# Battery_Manager.net
KiCad netlist of a schematic drawn in Altium Designer
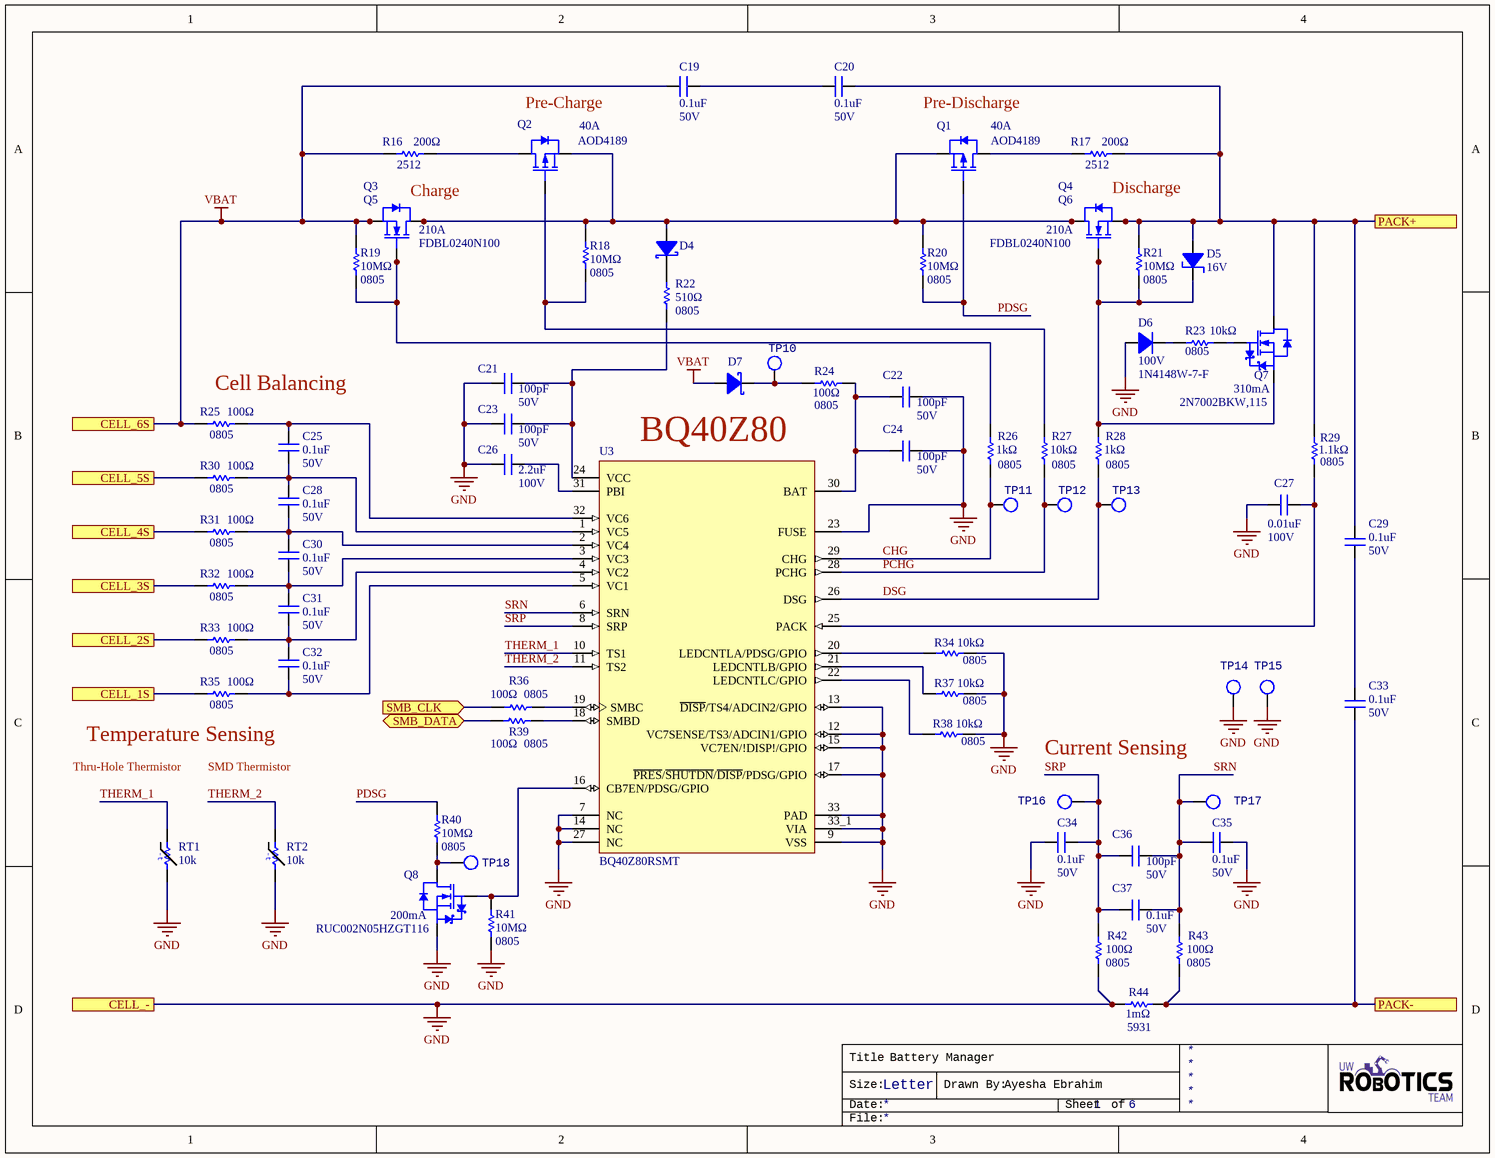
[diagram p0: Battery Manager.SchDoc]

(export (version "E")
  (design (tool "Eeschema 10.0.6"))
  (components
    (comp (ref "C19")
      (value "0.1uF")
      (footprint "CAPC2012X140N")
      (description "CAP CER 0.1UF 50V X7R 0805")
      (fields
        (field (name "TOLERANCE") "10%")
        (field (name "VOLTAGE RATING") "50V")
        (field (name "Comment") "CAP_0.1uF_50V_0805")
      )
      (libsource (lib "UWRT_Schematic_Library_2020") (part "CAP_0.1uF_50V_0805"))
    )
    (comp (ref "C20")
      (value "0.1uF")
      (footprint "CAPC2012X140N")
      (description "CAP CER 0.1UF 50V X7R 0805")
      (fields
        (field (name "TOLERANCE") "10%")
        (field (name "VOLTAGE RATING") "50V")
        (field (name "Comment") "CAP_0.1uF_50V_0805")
      )
      (libsource (lib "UWRT_Schematic_Library_2020") (part "CAP_0.1uF_50V_0805"))
    )
    (comp (ref "C21")
      (value "100pF")
      (footprint "CAPC2012X140N")
      (description "CAP CER 100PF 50V C0G/NP0 0805")
      (fields
        (field (name "TOLERANCE") "5%")
        (field (name "VOLTAGE RATING") "50V")
        (field (name "Comment") "CAP_100pF_50V_0805")
      )
      (libsource (lib "UWRT_Schematic_Library_2020") (part "CAP_100pF_50V_0805"))
    )
    (comp (ref "C22")
      (value "100pF")
      (footprint "CAPC2012X140N")
      (description "CAP CER 100PF 50V C0G/NP0 0805")
      (fields
        (field (name "TOLERANCE") "5%")
        (field (name "VOLTAGE RATING") "50V")
        (field (name "Comment") "CAP_100pF_50V_0805")
      )
      (libsource (lib "UWRT_Schematic_Library_2020") (part "CAP_100pF_50V_0805"))
    )
    (comp (ref "C23")
      (value "100pF")
      (footprint "CAPC2012X140N")
      (description "CAP CER 100PF 50V C0G/NP0 0805")
      (fields
        (field (name "TOLERANCE") "5%")
        (field (name "VOLTAGE RATING") "50V")
        (field (name "Comment") "CAP_100pF_50V_0805")
      )
      (libsource (lib "UWRT_Schematic_Library_2020") (part "CAP_100pF_50V_0805"))
    )
    (comp (ref "C24")
      (value "100pF")
      (footprint "CAPC2012X140N")
      (description "CAP CER 100PF 50V C0G/NP0 0805")
      (fields
        (field (name "TOLERANCE") "5%")
        (field (name "VOLTAGE RATING") "50V")
        (field (name "Comment") "CAP_100pF_50V_0805")
      )
      (libsource (lib "UWRT_Schematic_Library_2020") (part "CAP_100pF_50V_0805"))
    )
    (comp (ref "C25")
      (value "0.1uF")
      (footprint "CAPC2012X140N")
      (description "CAP CER 0.1UF 50V X7R 0805")
      (fields
        (field (name "TOLERANCE") "10%")
        (field (name "VOLTAGE RATING") "50V")
        (field (name "Comment") "CAP_0.1uF_50V_0805")
      )
      (libsource (lib "UWRT_Schematic_Library_2020") (part "CAP_0.1uF_50V_0805"))
    )
    (comp (ref "C26")
      (value "2.2uF")
      (footprint "CAPC1210(3225)")
      (description "CAP CER 2.2UF 100V X7R 1210")
      (fields
        (field (name "TOLERANCE") "10%")
        (field (name "VOLTAGE RATING") "100V")
        (field (name "Comment") "CAP_2.2uF_100V_1210")
      )
      (libsource (lib "UWRT_Schematic_Library_2020") (part "CAP_2.2uF_100V_1210"))
    )
    (comp (ref "C27")
      (value "0.01uF")
      (footprint "CAPC2012X140N")
      (description "CAP CER 10000PF 100V X7R 0805")
      (fields
        (field (name "TOLERANCE") "10%")
        (field (name "VOLTAGE RATING") "100V")
        (field (name "Comment") "CAP_0.01uF_100V_0805")
      )
      (libsource (lib "UWRT_Schematic_Library_2020") (part "CAP_0.01uF_100V_0805"))
    )
    (comp (ref "C28")
      (value "0.1uF")
      (footprint "CAPC2012X140N")
      (description "CAP CER 0.1UF 50V X7R 0805")
      (fields
        (field (name "TOLERANCE") "10%")
        (field (name "VOLTAGE RATING") "50V")
        (field (name "Comment") "CAP_0.1uF_50V_0805")
      )
      (libsource (lib "UWRT_Schematic_Library_2020") (part "CAP_0.1uF_50V_0805"))
    )
    (comp (ref "C29")
      (value "0.1uF")
      (footprint "CAPC2012X140N")
      (description "CAP CER 0.1UF 50V X7R 0805")
      (fields
        (field (name "TOLERANCE") "10%")
        (field (name "VOLTAGE RATING") "50V")
        (field (name "Comment") "CAP_0.1uF_50V_0805")
      )
      (libsource (lib "UWRT_Schematic_Library_2020") (part "CAP_0.1uF_50V_0805"))
    )
    (comp (ref "C30")
      (value "0.1uF")
      (footprint "CAPC2012X140N")
      (description "CAP CER 0.1UF 50V X7R 0805")
      (fields
        (field (name "TOLERANCE") "10%")
        (field (name "VOLTAGE RATING") "50V")
        (field (name "Comment") "CAP_0.1uF_50V_0805")
      )
      (libsource (lib "UWRT_Schematic_Library_2020") (part "CAP_0.1uF_50V_0805"))
    )
    (comp (ref "C31")
      (value "0.1uF")
      (footprint "CAPC2012X140N")
      (description "CAP CER 0.1UF 50V X7R 0805")
      (fields
        (field (name "TOLERANCE") "10%")
        (field (name "VOLTAGE RATING") "50V")
        (field (name "Comment") "CAP_0.1uF_50V_0805")
      )
      (libsource (lib "UWRT_Schematic_Library_2020") (part "CAP_0.1uF_50V_0805"))
    )
    (comp (ref "C32")
      (value "0.1uF")
      (footprint "CAPC2012X140N")
      (description "CAP CER 0.1UF 50V X7R 0805")
      (fields
        (field (name "TOLERANCE") "10%")
        (field (name "VOLTAGE RATING") "50V")
        (field (name "Comment") "CAP_0.1uF_50V_0805")
      )
      (libsource (lib "UWRT_Schematic_Library_2020") (part "CAP_0.1uF_50V_0805"))
    )
    (comp (ref "C33")
      (value "0.1uF")
      (footprint "CAPC2012X140N")
      (description "CAP CER 0.1UF 50V X7R 0805")
      (fields
        (field (name "TOLERANCE") "10%")
        (field (name "VOLTAGE RATING") "50V")
        (field (name "Comment") "CAP_0.1uF_50V_0805")
      )
      (libsource (lib "UWRT_Schematic_Library_2020") (part "CAP_0.1uF_50V_0805"))
    )
    (comp (ref "C34")
      (value "0.1uF")
      (footprint "CAPC2012X140N")
      (description "CAP CER 0.1UF 50V X7R 0805")
      (fields
        (field (name "TOLERANCE") "10%")
        (field (name "VOLTAGE RATING") "50V")
        (field (name "Comment") "CAP_0.1uF_50V_0805")
      )
      (libsource (lib "UWRT_Schematic_Library_2020") (part "CAP_0.1uF_50V_0805"))
    )
    (comp (ref "C35")
      (value "0.1uF")
      (footprint "CAPC2012X140N")
      (description "CAP CER 0.1UF 50V X7R 0805")
      (fields
        (field (name "TOLERANCE") "10%")
        (field (name "VOLTAGE RATING") "50V")
        (field (name "Comment") "CAP_0.1uF_50V_0805")
      )
      (libsource (lib "UWRT_Schematic_Library_2020") (part "CAP_0.1uF_50V_0805"))
    )
    (comp (ref "C36")
      (value "100pF")
      (footprint "CAPC2012X140N")
      (description "CAP CER 100PF 50V C0G/NP0 0805")
      (fields
        (field (name "TOLERANCE") "5%")
        (field (name "VOLTAGE RATING") "50V")
        (field (name "Comment") "CAP_100pF_50V_0805")
      )
      (libsource (lib "UWRT_Schematic_Library_2020") (part "CAP_100pF_50V_0805"))
    )
    (comp (ref "C37")
      (value "0.1uF")
      (footprint "CAPC2012X140N")
      (description "CAP CER 0.1UF 50V X7R 0805")
      (fields
        (field (name "TOLERANCE") "10%")
        (field (name "VOLTAGE RATING") "50V")
        (field (name "Comment") "CAP_0.1uF_50V_0805")
      )
      (libsource (lib "UWRT_Schematic_Library_2020") (part "CAP_0.1uF_50V_0805"))
    )
    (comp (ref "D4")
      (value "B0540W-7-F")
      (footprint "SOD-123_FLAT")
      (description "DIODE SCHOTTKY 40V 500MA SOD123")
      (fields
        (field (name "MANUFACTURER") "Diodes Inc.")
        (field (name "OCTOPART") "https://octopart.com/b0540w-7-f-diodes+inc.-325656")
      )
      (libsource (lib "UWRT_Schematic_Library_2020") (part "DIO_SCHOTTKY_40V_500mA"))
    )
    (comp (ref "D5")
      (value "DIO_ZENER_16V")
      (footprint "SOD-123_FLAT")
      (description "DIODE ZENER 16V 500MW SOD123")
      (fields (field (name "ZENER VOLTAGE") "16V") (field (name "TOLERANCE") "5%"))
      (libsource (lib "UWRT_Schematic_Library_2020") (part "DIO_ZENER_16V"))
    )
    (comp (ref "D6")
      (value "100V")
      (footprint "SOD-123_FLAT")
      (description "DIODE GEN PURP 100V 300MA SOD123")
      (fields
        (field (name "MANUFACTURER PART NUMBER 1") "1N4148W-7-F")
        (field (name "Comment") "1N4148W-7-F")
      )
      (libsource (lib "UWRT_Schematic_Library_2020") (part "DIO_100V_300mA"))
    )
    (comp (ref "D7")
      (value "B0540W-7-F")
      (footprint "SOD-123_FLAT")
      (description "DIODE SCHOTTKY 40V 500MA SOD123")
      (fields
        (field (name "MANUFACTURER") "Diodes Inc.")
        (field (name "OCTOPART") "https://octopart.com/b0540w-7-f-diodes+inc.-325656")
      )
      (libsource (lib "UWRT_Schematic_Library_2020") (part "DIO_SCHOTTKY_40V_500mA"))
    )
    (comp (ref "Q1")
      (value "PMOS_40V_40A")
      (footprint "D-PAK")
      (description "MOSFET P-CH 40V 40A TO252")
      (fields (field (name "MANUFACTURER PART NUMBER 1") "AOD4189") (field (name "ID") "40A"))
      (libsource (lib "UWRT_Schematic_Library_2020") (part "PMOS_40V_40A"))
    )
    (comp (ref "Q2")
      (value "PMOS_40V_40A")
      (footprint "D-PAK")
      (description "MOSFET P-CH 40V 40A TO252")
      (fields (field (name "MANUFACTURER PART NUMBER 1") "AOD4189") (field (name "ID") "40A"))
      (libsource (lib "UWRT_Schematic_Library_2020") (part "PMOS_40V_40A"))
    )
    (comp (ref "Q3")
      (value "NMOS_100V_210A")
      (footprint "8-HPSOF")
      (description "MOSFET N-CH 100V 210A POWER56")
      (fields (field (name "MANUFACTURER PART NUMBER 1") "FDBL0240N100") (field (name "ID") "210A"))
      (libsource (lib "UWRT_Schematic_Library_2020") (part "NMOS_100V_210A"))
    )
    (comp (ref "Q4")
      (value "NMOS_100V_210A")
      (footprint "8-HPSOF")
      (description "MOSFET N-CH 100V 210A POWER56")
      (fields (field (name "MANUFACTURER PART NUMBER 1") "FDBL0240N100") (field (name "ID") "210A"))
      (libsource (lib "UWRT_Schematic_Library_2020") (part "NMOS_100V_210A"))
    )
    (comp (ref "Q5")
      (value "NMOS_100V_210A")
      (footprint "8-HPSOF")
      (description "MOSFET N-CH 100V 210A POWER56")
      (libsource (lib "UWRT_Schematic_Library_2020") (part "NMOS_100V_210A"))
    )
    (comp (ref "Q6")
      (value "NMOS_100V_210A")
      (footprint "8-HPSOF")
      (description "MOSFET N-CH 100V 210A POWER56")
      (libsource (lib "UWRT_Schematic_Library_2020") (part "NMOS_100V_210A"))
    )
    (comp (ref "Q7")
      (value "NMOS_60V_310mA")
      (footprint "SOT323")
      (description "NMOS N-CH 60V 310mA SOT-323")
      (fields (field (name "MANUFACTURER PART NUMBER 1") "2N7002BKW,115") (field (name "ID") "310mA"))
      (libsource (lib "UWRT_Schematic_Library_2020") (part "NMOS_60V_310mA"))
    )
    (comp (ref "Q8")
      (value "NMOS_50V_200mA")
      (footprint "SOT23-3")
      (description "NMOS N-CH 50V 200mA 1.2V DRIVE SOT-23-3")
      (fields (field (name "MANUFACTURER PART NUMBER 1") "RUC002N05HZGT116") (field (name "ID") "200mA"))
      (libsource (lib "UWRT_Schematic_Library_2020") (part "NMOS_50V_200mA"))
    )
    (comp (ref "R16")
      (value "200Ω")
      (footprint "RESC6532X75N")
      (description "RES 200 OHM 5% 1W 2512")
      (fields
        (field (name "PACKAGE") "2512")
        (field (name "TOLERANCE") "5%")
        (field (name "Comment") "RES_200Ω_2512")
      )
      (libsource (lib "UWRT_Schematic_Library_2020") (part "RES_200Ω_2512"))
    )
    (comp (ref "R17")
      (value "200Ω")
      (footprint "RESC6532X75N")
      (description "RES 200 OHM 5% 1W 2512")
      (fields
        (field (name "PACKAGE") "2512")
        (field (name "TOLERANCE") "5%")
        (field (name "Comment") "RES_200Ω_2512")
      )
      (libsource (lib "UWRT_Schematic_Library_2020") (part "RES_200Ω_2512"))
    )
    (comp (ref "R18")
      (value "10MΩ")
      (footprint "RESC2012X60N")
      (description "RES SMD 10M OHM 5% 1/8W 0805")
      (fields
        (field (name "TOLERANCE") "5%")
        (field (name "CASE CODE (IMPERIAL)") "0805")
        (field (name "Comment") "RES_10MΩ_0805")
      )
      (libsource (lib "UWRT_Schematic_Library_2020") (part "RES_10MΩ_0805"))
    )
    (comp (ref "R19")
      (value "10MΩ")
      (footprint "RESC2012X60N")
      (description "RES SMD 10M OHM 5% 1/8W 0805")
      (fields
        (field (name "TOLERANCE") "5%")
        (field (name "CASE CODE (IMPERIAL)") "0805")
        (field (name "Comment") "RES_10MΩ_0805")
      )
      (libsource (lib "UWRT_Schematic_Library_2020") (part "RES_10MΩ_0805"))
    )
    (comp (ref "R20")
      (value "10MΩ")
      (footprint "RESC2012X60N")
      (description "RES SMD 10M OHM 5% 1/8W 0805")
      (fields
        (field (name "TOLERANCE") "5%")
        (field (name "CASE CODE (IMPERIAL)") "0805")
        (field (name "Comment") "RES_10MΩ_0805")
      )
      (libsource (lib "UWRT_Schematic_Library_2020") (part "RES_10MΩ_0805"))
    )
    (comp (ref "R21")
      (value "10MΩ")
      (footprint "RESC2012X60N")
      (description "RES SMD 10M OHM 5% 1/8W 0805")
      (fields
        (field (name "TOLERANCE") "5%")
        (field (name "CASE CODE (IMPERIAL)") "0805")
        (field (name "Comment") "RES_10MΩ_0805")
      )
      (libsource (lib "UWRT_Schematic_Library_2020") (part "RES_10MΩ_0805"))
    )
    (comp (ref "R22")
      (value "510Ω")
      (footprint "RESC2012X60N")
      (description "RES SMD 510 OHM 1% 1/8W 0805")
      (fields
        (field (name "CASE CODE (IMPERIAL)") "0805")
        (field (name "TOLERANCE") "1%")
        (field (name "Comment") "RES_510Ω_0805")
      )
      (libsource (lib "UWRT_Schematic_Library_2020") (part "RES_510Ω_0805"))
    )
    (comp (ref "R23")
      (value "10kΩ")
      (footprint "RESC2012X60N")
      (description "RES SMD 10K OHM 1% 1/8W 0805")
      (fields
        (field (name "CASE CODE (IMPERIAL)") "0805")
        (field (name "TOLERANCE") "1%")
        (field (name "Comment") "RES_10kΩ_0805")
      )
      (libsource (lib "UWRT_Schematic_Library_2020") (part "RES_10kΩ_0805"))
    )
    (comp (ref "R24")
      (value "100Ω")
      (footprint "RESC2012X60N")
      (description "RES SMD 100 OHM 1% 1/8W 0805")
      (fields (field (name "CASE CODE (IMPERIAL)") "0805") (field (name "Comment") "RES_100Ω_0805"))
      (libsource (lib "UWRT_Schematic_Library_2020") (part "RES_100Ω_0805"))
    )
    (comp (ref "R25")
      (value "100Ω")
      (footprint "RESC2012X60N")
      (description "RES SMD 100 OHM 1% 1/8W 0805")
      (fields (field (name "CASE CODE (IMPERIAL)") "0805") (field (name "Comment") "RES_100Ω_0805"))
      (libsource (lib "UWRT_Schematic_Library_2020") (part "RES_100Ω_0805"))
    )
    (comp (ref "R26")
      (value "1kΩ")
      (footprint "RESC2012X60N")
      (description "RES SMD 1K OHM 1% 1/8W 0805")
      (fields
        (field (name "CASE CODE (IMPERIAL)") "0805")
        (field (name "TOLERANCE") "1%")
        (field (name "Comment") "RES_1kΩ_0805")
      )
      (libsource (lib "UWRT_Schematic_Library_2020") (part "RES_1kΩ_0805"))
    )
    (comp (ref "R27")
      (value "10kΩ")
      (footprint "RESC2012X60N")
      (description "RES SMD 10K OHM 1% 1/8W 0805")
      (fields
        (field (name "CASE CODE (IMPERIAL)") "0805")
        (field (name "TOLERANCE") "1%")
        (field (name "Comment") "RES_10kΩ_0805")
      )
      (libsource (lib "UWRT_Schematic_Library_2020") (part "RES_10kΩ_0805"))
    )
    (comp (ref "R28")
      (value "1kΩ")
      (footprint "RESC2012X60N")
      (description "RES SMD 1K OHM 1% 1/8W 0805")
      (fields
        (field (name "CASE CODE (IMPERIAL)") "0805")
        (field (name "TOLERANCE") "1%")
        (field (name "Comment") "RES_1kΩ_0805")
      )
      (libsource (lib "UWRT_Schematic_Library_2020") (part "RES_1kΩ_0805"))
    )
    (comp (ref "R29")
      (value "1.1kΩ")
      (footprint "RESC2012X60N")
      (description "RES SMD 1.1K OHM 1% 1/8W 0805")
      (fields
        (field (name "CASE CODE (IMPERIAL)") "0805")
        (field (name "TOLERANCE") "1%")
        (field (name "Comment") "RES_1.1kΩ_0805")
      )
      (libsource (lib "UWRT_Schematic_Library_2020") (part "RES_1.1kΩ_0805"))
    )
    (comp (ref "R30")
      (value "100Ω")
      (footprint "RESC2012X60N")
      (description "RES SMD 100 OHM 1% 1/8W 0805")
      (fields (field (name "CASE CODE (IMPERIAL)") "0805") (field (name "Comment") "RES_100Ω_0805"))
      (libsource (lib "UWRT_Schematic_Library_2020") (part "RES_100Ω_0805"))
    )
    (comp (ref "R31")
      (value "100Ω")
      (footprint "RESC2012X60N")
      (description "RES SMD 100 OHM 1% 1/8W 0805")
      (fields (field (name "CASE CODE (IMPERIAL)") "0805") (field (name "Comment") "RES_100Ω_0805"))
      (libsource (lib "UWRT_Schematic_Library_2020") (part "RES_100Ω_0805"))
    )
    (comp (ref "R32")
      (value "100Ω")
      (footprint "RESC2012X60N")
      (description "RES SMD 100 OHM 1% 1/8W 0805")
      (fields (field (name "CASE CODE (IMPERIAL)") "0805") (field (name "Comment") "RES_100Ω_0805"))
      (libsource (lib "UWRT_Schematic_Library_2020") (part "RES_100Ω_0805"))
    )
    (comp (ref "R33")
      (value "100Ω")
      (footprint "RESC2012X60N")
      (description "RES SMD 100 OHM 1% 1/8W 0805")
      (fields (field (name "CASE CODE (IMPERIAL)") "0805") (field (name "Comment") "RES_100Ω_0805"))
      (libsource (lib "UWRT_Schematic_Library_2020") (part "RES_100Ω_0805"))
    )
    (comp (ref "R34")
      (value "10kΩ")
      (footprint "RESC2012X60N")
      (description "RES SMD 10K OHM 1% 1/8W 0805")
      (fields
        (field (name "CASE CODE (IMPERIAL)") "0805")
        (field (name "TOLERANCE") "1%")
        (field (name "Comment") "RES_10kΩ_0805")
      )
      (libsource (lib "UWRT_Schematic_Library_2020") (part "RES_10kΩ_0805"))
    )
    (comp (ref "R35")
      (value "100Ω")
      (footprint "RESC2012X60N")
      (description "RES SMD 100 OHM 1% 1/8W 0805")
      (fields (field (name "CASE CODE (IMPERIAL)") "0805") (field (name "Comment") "RES_100Ω_0805"))
      (libsource (lib "UWRT_Schematic_Library_2020") (part "RES_100Ω_0805"))
    )
    (comp (ref "R36")
      (value "100Ω")
      (footprint "RESC2012X60N")
      (description "RES SMD 100 OHM 1% 1/8W 0805")
      (fields (field (name "CASE CODE (IMPERIAL)") "0805") (field (name "Comment") "RES_100Ω_0805"))
      (libsource (lib "UWRT_Schematic_Library_2020") (part "RES_100Ω_0805"))
    )
    (comp (ref "R37")
      (value "10kΩ")
      (footprint "RESC2012X60N")
      (description "RES SMD 10K OHM 1% 1/8W 0805")
      (fields
        (field (name "CASE CODE (IMPERIAL)") "0805")
        (field (name "TOLERANCE") "1%")
        (field (name "Comment") "RES_10kΩ_0805")
      )
      (libsource (lib "UWRT_Schematic_Library_2020") (part "RES_10kΩ_0805"))
    )
    (comp (ref "R38")
      (value "10kΩ")
      (footprint "RESC2012X60N")
      (description "RES SMD 10K OHM 1% 1/8W 0805")
      (fields
        (field (name "CASE CODE (IMPERIAL)") "0805")
        (field (name "TOLERANCE") "1%")
        (field (name "Comment") "RES_10kΩ_0805")
      )
      (libsource (lib "UWRT_Schematic_Library_2020") (part "RES_10kΩ_0805"))
    )
    (comp (ref "R39")
      (value "100Ω")
      (footprint "RESC2012X60N")
      (description "RES SMD 100 OHM 1% 1/8W 0805")
      (fields (field (name "CASE CODE (IMPERIAL)") "0805") (field (name "Comment") "RES_100Ω_0805"))
      (libsource (lib "UWRT_Schematic_Library_2020") (part "RES_100Ω_0805"))
    )
    (comp (ref "R40")
      (value "10MΩ")
      (footprint "RESC2012X60N")
      (description "RES SMD 10M OHM 5% 1/8W 0805")
      (fields
        (field (name "TOLERANCE") "5%")
        (field (name "CASE CODE (IMPERIAL)") "0805")
        (field (name "Comment") "RES_10MΩ_0805")
      )
      (libsource (lib "UWRT_Schematic_Library_2020") (part "RES_10MΩ_0805"))
    )
    (comp (ref "R41")
      (value "10MΩ")
      (footprint "RESC2012X60N")
      (description "RES SMD 10M OHM 5% 1/8W 0805")
      (fields
        (field (name "TOLERANCE") "5%")
        (field (name "CASE CODE (IMPERIAL)") "0805")
        (field (name "Comment") "RES_10MΩ_0805")
      )
      (libsource (lib "UWRT_Schematic_Library_2020") (part "RES_10MΩ_0805"))
    )
    (comp (ref "R42")
      (value "100Ω")
      (footprint "RESC2012X60N")
      (description "RES SMD 100 OHM 1% 1/8W 0805")
      (fields (field (name "CASE CODE (IMPERIAL)") "0805") (field (name "Comment") "RES_100Ω_0805"))
      (libsource (lib "UWRT_Schematic_Library_2020") (part "RES_100Ω_0805"))
    )
    (comp (ref "R43")
      (value "100Ω")
      (footprint "RESC2012X60N")
      (description "RES SMD 100 OHM 1% 1/8W 0805")
      (fields (field (name "CASE CODE (IMPERIAL)") "0805") (field (name "Comment") "RES_100Ω_0805"))
      (libsource (lib "UWRT_Schematic_Library_2020") (part "RES_100Ω_0805"))
    )
    (comp (ref "R44")
      (value "1mΩ")
      (footprint "RES-5931")
      (description "RES 0.001 OHM 1% 10W 5931")
      (fields
        (field (name "PACKAGE") "5931")
        (field (name "TOLERANCE") "1%")
        (field (name "Comment") "RES_1mΩ_5931")
      )
      (libsource (lib "UWRT_Schematic_Library_2020") (part "RES_1mΩ_5931"))
    )
    (comp (ref "RT1")
      (value "THERM_10k_FREE_HANGING")
      (footprint "HDR1X2 - PTH Thermistor")
      (description "THERMISTOR NTC 10KOHM 3380K BEAD")
      (fields (field (name "TOLERANCE") "1%") (field (name "RESISTANCE") "10k"))
      (libsource (lib "UWRT_Schematic_Library_2020") (part "THERM_10k_FREE_HANGING"))
    )
    (comp (ref "RT2")
      (value "THERM_10k_0603")
      (footprint "RESC0603(1608)_N")
      (description "THERMISTOR NTC 10K 1% OHM 0603")
      (fields (field (name "TOLERANCE") "1%") (field (name "RESISTANCE") "10k"))
      (libsource (lib "UWRT_Schematic_Library_2020") (part "THERM_10k_0603"))
    )
    (comp (ref "TP10")
      (value "TESTPOINT_LOOP")
      (footprint "TESTPOINT_LOOP")
      (description "Loop testpoint through-hole pad")
      (libsource (lib "UWRT_Schematic_Library_2020") (part "TESTPOINT_LOOP"))
    )
    (comp (ref "TP11")
      (value "TESTPOINT_LOOP")
      (footprint "TESTPOINT_LOOP")
      (description "Loop testpoint through-hole pad")
      (libsource (lib "UWRT_Schematic_Library_2020") (part "TESTPOINT_LOOP"))
    )
    (comp (ref "TP12")
      (value "TESTPOINT_LOOP")
      (footprint "TESTPOINT_LOOP")
      (description "Loop testpoint through-hole pad")
      (libsource (lib "UWRT_Schematic_Library_2020") (part "TESTPOINT_LOOP"))
    )
    (comp (ref "TP13")
      (value "TESTPOINT_LOOP")
      (footprint "TESTPOINT_LOOP")
      (description "Loop testpoint through-hole pad")
      (libsource (lib "UWRT_Schematic_Library_2020") (part "TESTPOINT_LOOP"))
    )
    (comp (ref "TP14")
      (value "TESTPOINT_LOOP")
      (footprint "TESTPOINT_LOOP")
      (description "Loop testpoint through-hole pad")
      (libsource (lib "UWRT_Schematic_Library_2020") (part "TESTPOINT_LOOP"))
    )
    (comp (ref "TP15")
      (value "TESTPOINT_LOOP")
      (footprint "TESTPOINT_LOOP")
      (description "Loop testpoint through-hole pad")
      (libsource (lib "UWRT_Schematic_Library_2020") (part "TESTPOINT_LOOP"))
    )
    (comp (ref "TP16")
      (value "TESTPOINT_LOOP")
      (footprint "TESTPOINT_LOOP")
      (description "Loop testpoint through-hole pad")
      (libsource (lib "UWRT_Schematic_Library_2020") (part "TESTPOINT_LOOP"))
    )
    (comp (ref "TP17")
      (value "TESTPOINT_LOOP")
      (footprint "TESTPOINT_LOOP")
      (description "Loop testpoint through-hole pad")
      (libsource (lib "UWRT_Schematic_Library_2020") (part "TESTPOINT_LOOP"))
    )
    (comp (ref "TP18")
      (value "TESTPOINT_LOOP")
      (footprint "TESTPOINT_LOOP")
      (description "Loop testpoint through-hole pad")
      (libsource (lib "UWRT_Schematic_Library_2020") (part "TESTPOINT_LOOP"))
    )
    (comp (ref "U3")
      (value "BQ40Z80RSMT")
      (footprint "BQ40Z80RSMT")
      (description "POWER MANAGEMENT IC: Battery Multi-Function Controller IC Lithium Ion/Polymer 32-VQFN (4x4)")
      (libsource (lib "UWRT_Schematic_Library_2020") (part "BATT_MANAGER"))
    )
  )
  (nets
    (net (code "1") (name "/CELL_1S") (class "Default")
      (node (ref "R35") (pin "1") (pinfunction "1_1") (pintype "passive"))
    )
    (net (code "2") (name "/CELL_2S") (class "Default")
      (node (ref "R33") (pin "1") (pinfunction "1_1") (pintype "passive"))
    )
    (net (code "3") (name "/CELL_3S") (class "Default")
      (node (ref "R32") (pin "1") (pinfunction "1_1") (pintype "passive"))
    )
    (net (code "4") (name "/CELL_4S") (class "Default")
      (node (ref "R31") (pin "1") (pinfunction "1_1") (pintype "passive"))
    )
    (net (code "5") (name "/CELL_5S") (class "Default")
      (node (ref "R30") (pin "1") (pinfunction "1_1") (pintype "passive"))
    )
    (net (code "6") (name "/CHG") (class "Default")
      (node (ref "R26") (pin "1") (pinfunction "1_1") (pintype "passive"))
      (node (ref "TP11") (pin "1") (pintype "passive"))
      (node (ref "U3") (pin "29") (pinfunction "CHG_29") (pintype "output"))
    )
    (net (code "7") (name "/DSG") (class "Default")
      (node (ref "R28") (pin "1") (pinfunction "1_1") (pintype "passive"))
      (node (ref "TP13") (pin "1") (pintype "passive"))
      (node (ref "U3") (pin "26") (pinfunction "DSG_26") (pintype "output"))
    )
    (net (code "8") (name "/PACK+") (class "Default")
      (node (ref "C20") (pin "2") (pinfunction "2_2") (pintype "passive"))
      (node (ref "C29") (pin "2") (pinfunction "2_2") (pintype "passive"))
      (node (ref "D5") (pin "1") (pinfunction "Anode_1") (pintype "passive"))
      (node (ref "Q4") (pin "2") (pinfunction "Source_2") (pintype "passive"))
      (node (ref "Q6") (pin "2") (pinfunction "Source_2") (pintype "passive"))
      (node (ref "Q7") (pin "3") (pinfunction "D_3") (pintype "passive"))
      (node (ref "R17") (pin "2") (pinfunction "2_2") (pintype "passive"))
      (node (ref "R21") (pin "2") (pinfunction "2_2") (pintype "passive"))
      (node (ref "R29") (pin "2") (pinfunction "2_2") (pintype "passive"))
    )
    (net (code "9") (name "/PACK-") (class "Default")
      (node (ref "C33") (pin "1") (pinfunction "1_1") (pintype "passive"))
      (node (ref "R43") (pin "1") (pinfunction "1_1") (pintype "passive"))
      (node (ref "R44") (pin "2") (pinfunction "2_2") (pintype "passive"))
    )
    (net (code "10") (name "/PCHG") (class "Default")
      (node (ref "R27") (pin "1") (pinfunction "1_1") (pintype "passive"))
      (node (ref "TP12") (pin "1") (pintype "passive"))
      (node (ref "U3") (pin "28") (pinfunction "PCHG_28") (pintype "output"))
    )
    (net (code "11") (name "/PDSG") (class "Default")
      (node (ref "Q1") (pin "2") (pinfunction "Gate_2") (pintype "passive"))
      (node (ref "R20") (pin "1") (pinfunction "1_1") (pintype "passive"))
      (node (ref "R40") (pin "2") (pinfunction "2_2") (pintype "passive"))
    )
    (net (code "12") (name "/SMB_CLK") (class "Default")
      (node (ref "R36") (pin "1") (pinfunction "1_1") (pintype "passive"))
    )
    (net (code "13") (name "/SMB_DATA") (class "Default")
      (node (ref "R39") (pin "1") (pinfunction "1_1") (pintype "passive"))
    )
    (net (code "14") (name "/SRN") (class "Default")
      (node (ref "C35") (pin "1") (pinfunction "1_1") (pintype "passive"))
      (node (ref "C36") (pin "2") (pinfunction "2_2") (pintype "passive"))
      (node (ref "C37") (pin "2") (pinfunction "2_2") (pintype "passive"))
      (node (ref "R43") (pin "2") (pinfunction "2_2") (pintype "passive"))
      (node (ref "TP17") (pin "1") (pintype "passive"))
      (node (ref "U3") (pin "6") (pinfunction "SRN_6") (pintype "input"))
    )
    (net (code "15") (name "/SRP") (class "Default")
      (node (ref "C34") (pin "2") (pinfunction "2_2") (pintype "passive"))
      (node (ref "C36") (pin "1") (pinfunction "1_1") (pintype "passive"))
      (node (ref "C37") (pin "1") (pinfunction "1_1") (pintype "passive"))
      (node (ref "R42") (pin "2") (pinfunction "2_2") (pintype "passive"))
      (node (ref "TP16") (pin "1") (pintype "passive"))
      (node (ref "U3") (pin "8") (pinfunction "SRP_8") (pintype "input"))
    )
    (net (code "16") (name "/THERM_1") (class "Default")
      (node (ref "RT1") (pin "1") (pinfunction "1_1") (pintype "passive"))
      (node (ref "U3") (pin "10") (pinfunction "TS1_10") (pintype "input"))
    )
    (net (code "17") (name "/THERM_2") (class "Default")
      (node (ref "RT2") (pin "1") (pinfunction "1_1") (pintype "passive"))
      (node (ref "U3") (pin "11") (pinfunction "TS2_11") (pintype "input"))
    )
    (net (code "18") (name "GND") (class "Default")
      (node (ref "C21") (pin "1") (pinfunction "1_1") (pintype "passive"))
      (node (ref "C22") (pin "2") (pinfunction "2_2") (pintype "passive"))
      (node (ref "C23") (pin "1") (pinfunction "1_1") (pintype "passive"))
      (node (ref "C24") (pin "2") (pinfunction "2_2") (pintype "passive"))
      (node (ref "C26") (pin "1") (pinfunction "1_1") (pintype "passive"))
      (node (ref "C27") (pin "1") (pinfunction "1_1") (pintype "passive"))
      (node (ref "C34") (pin "1") (pinfunction "1_1") (pintype "passive"))
      (node (ref "C35") (pin "2") (pinfunction "2_2") (pintype "passive"))
      (node (ref "D6") (pin "2") (pintype "passive"))
      (node (ref "Q8") (pin "2") (pinfunction "S_2") (pintype "passive"))
      (node (ref "R34") (pin "2") (pinfunction "2_2") (pintype "passive"))
      (node (ref "R37") (pin "2") (pinfunction "2_2") (pintype "passive"))
      (node (ref "R38") (pin "2") (pinfunction "2_2") (pintype "passive"))
      (node (ref "R41") (pin "1") (pinfunction "1_1") (pintype "passive"))
      (node (ref "R42") (pin "1") (pinfunction "1_1") (pintype "passive"))
      (node (ref "R44") (pin "1") (pinfunction "1_1") (pintype "passive"))
      (node (ref "RT1") (pin "2") (pinfunction "2_2") (pintype "passive"))
      (node (ref "RT2") (pin "2") (pinfunction "2_2") (pintype "passive"))
      (node (ref "TP14") (pin "1") (pintype "passive"))
      (node (ref "TP15") (pin "1") (pintype "passive"))
      (node (ref "U3") (pin "12") (pinfunction "VC7SENSE/TS3/ADCIN1/GPIO_12") (pintype "bidirectional"))
      (node (ref "U3") (pin "13") (pinfunction "~{DISP}/TS4/ADCIN2/GPIO_13") (pintype "bidirectional"))
      (node (ref "U3") (pin "14") (pinfunction "NC_14") (pintype "passive"))
      (node (ref "U3") (pin "15") (pinfunction "VC7EN/!DISP!/GPIO_15") (pintype "bidirectional"))
      (node (ref "U3") (pin "17") (pinfunction "~{PRES}/~{SHUTDN}/~{DISP}/PDSG/GPIO_17") (pintype "bidirectional"))
      (node (ref "U3") (pin "23") (pinfunction "FUSE_23") (pintype "passive"))
      (node (ref "U3") (pin "27") (pinfunction "NC_27") (pintype "passive"))
      (node (ref "U3") (pin "33") (pinfunction "PAD_33") (pintype "power_in"))
      (node (ref "U3") (pin "33_1") (pinfunction "VIA_33_1") (pintype "power_in"))
      (node (ref "U3") (pin "7") (pinfunction "NC_7") (pintype "passive"))
      (node (ref "U3") (pin "9") (pinfunction "VSS_9") (pintype "power_in"))
    )
    (net (code "19") (name "Net-(C19-Pad2)") (class "Default")
      (node (ref "C19") (pin "2") (pinfunction "2_2") (pintype "passive"))
      (node (ref "C20") (pin "1") (pinfunction "1_1") (pintype "passive"))
    )
    (net (code "20") (name "Net-(C29-Pad1)") (class "Default")
      (node (ref "C29") (pin "1") (pinfunction "1_1") (pintype "passive"))
      (node (ref "C33") (pin "2") (pinfunction "2_2") (pintype "passive"))
    )
    (net (code "21") (name "Net-(D4-Pad1)") (class "Default")
      (node (ref "D4") (pin "1") (pintype "passive"))
      (node (ref "R22") (pin "2") (pinfunction "2_2") (pintype "passive"))
    )
    (net (code "22") (name "Net-(D5-Cathode)") (class "Default")
      (node (ref "D5") (pin "2") (pinfunction "Cathode_2") (pintype "passive"))
      (node (ref "Q4") (pin "1") (pinfunction "Gate_1") (pintype "passive"))
      (node (ref "Q6") (pin "1") (pinfunction "Gate_1") (pintype "passive"))
      (node (ref "Q7") (pin "2") (pinfunction "S_2") (pintype "passive"))
      (node (ref "R21") (pin "1") (pinfunction "1_1") (pintype "passive"))
      (node (ref "R28") (pin "2") (pinfunction "2_2") (pintype "passive"))
    )
    (net (code "23") (name "Net-(D6-Pad1)") (class "Default")
      (node (ref "D6") (pin "1") (pintype "passive"))
      (node (ref "R23") (pin "1") (pinfunction "1_1") (pintype "passive"))
    )
    (net (code "24") (name "Net-(D7-Pad1)") (class "Default")
      (node (ref "D7") (pin "1") (pintype "passive"))
      (node (ref "R24") (pin "1") (pinfunction "1_1") (pintype "passive"))
      (node (ref "TP10") (pin "1") (pintype "passive"))
    )
    (net (code "25") (name "Net-(Q1-Drain)") (class "Default")
      (node (ref "Q1") (pin "1") (pinfunction "Drain_1") (pintype "passive"))
      (node (ref "R17") (pin "1") (pinfunction "1_1") (pintype "passive"))
    )
    (net (code "26") (name "Net-(Q1-Source)") (class "Default")
      (node (ref "D4") (pin "2") (pintype "passive"))
      (node (ref "Q1") (pin "3") (pinfunction "Source_3") (pintype "passive"))
      (node (ref "Q2") (pin "3") (pinfunction "Source_3") (pintype "passive"))
      (node (ref "Q3") (pin "3") (pinfunction "Drain_3") (pintype "passive"))
      (node (ref "Q4") (pin "3") (pinfunction "Drain_3") (pintype "passive"))
      (node (ref "Q5") (pin "3") (pinfunction "Drain_3") (pintype "passive"))
      (node (ref "Q6") (pin "3") (pinfunction "Drain_3") (pintype "passive"))
      (node (ref "R18") (pin "2") (pinfunction "2_2") (pintype "passive"))
      (node (ref "R20") (pin "2") (pinfunction "2_2") (pintype "passive"))
    )
    (net (code "27") (name "Net-(Q2-Drain)") (class "Default")
      (node (ref "Q2") (pin "1") (pinfunction "Drain_1") (pintype "passive"))
      (node (ref "R16") (pin "2") (pinfunction "2_2") (pintype "passive"))
    )
    (net (code "28") (name "Net-(Q2-Gate)") (class "Default")
      (node (ref "Q2") (pin "2") (pinfunction "Gate_2") (pintype "passive"))
      (node (ref "R18") (pin "1") (pinfunction "1_1") (pintype "passive"))
      (node (ref "R27") (pin "2") (pinfunction "2_2") (pintype "passive"))
    )
    (net (code "29") (name "Net-(Q3-Gate)") (class "Default")
      (node (ref "Q3") (pin "1") (pinfunction "Gate_1") (pintype "passive"))
      (node (ref "Q5") (pin "1") (pinfunction "Gate_1") (pintype "passive"))
      (node (ref "R19") (pin "1") (pinfunction "1_1") (pintype "passive"))
      (node (ref "R26") (pin "2") (pinfunction "2_2") (pintype "passive"))
    )
    (net (code "30") (name "Net-(Q7-G)") (class "Default")
      (node (ref "Q7") (pin "1") (pinfunction "G_1") (pintype "passive"))
      (node (ref "R23") (pin "2") (pinfunction "2_2") (pintype "passive"))
    )
    (net (code "31") (name "Net-(Q8-D)") (class "Default")
      (node (ref "Q8") (pin "3") (pinfunction "D_3") (pintype "passive"))
      (node (ref "R40") (pin "1") (pinfunction "1_1") (pintype "passive"))
      (node (ref "TP18") (pin "1") (pintype "passive"))
    )
    (net (code "32") (name "Net-(Q8-G)") (class "Default")
      (node (ref "Q8") (pin "1") (pinfunction "G_1") (pintype "passive"))
      (node (ref "R41") (pin "2") (pinfunction "2_2") (pintype "passive"))
      (node (ref "U3") (pin "16") (pinfunction "CB7EN/PDSG/GPIO_16") (pintype "bidirectional"))
    )
    (net (code "33") (name "Net-(U3-BAT)") (class "Default")
      (node (ref "C22") (pin "1") (pinfunction "1_1") (pintype "passive"))
      (node (ref "C24") (pin "1") (pinfunction "1_1") (pintype "passive"))
      (node (ref "R24") (pin "2") (pinfunction "2_2") (pintype "passive"))
      (node (ref "U3") (pin "30") (pinfunction "BAT_30") (pintype "power_in"))
    )
    (net (code "34") (name "Net-(U3-LEDCNTLA{slash}PDSG{slash}GPIO)") (class "Default")
      (node (ref "R34") (pin "1") (pinfunction "1_1") (pintype "passive"))
      (node (ref "U3") (pin "20") (pinfunction "LEDCNTLA/PDSG/GPIO_20") (pintype "output"))
    )
    (net (code "35") (name "Net-(U3-LEDCNTLB{slash}GPIO)") (class "Default")
      (node (ref "R37") (pin "1") (pinfunction "1_1") (pintype "passive"))
      (node (ref "U3") (pin "21") (pinfunction "LEDCNTLB/GPIO_21") (pintype "output"))
    )
    (net (code "36") (name "Net-(U3-LEDCNTLC{slash}GPIO)") (class "Default")
      (node (ref "R38") (pin "1") (pinfunction "1_1") (pintype "passive"))
      (node (ref "U3") (pin "22") (pinfunction "LEDCNTLC/GPIO_22") (pintype "output"))
    )
    (net (code "37") (name "Net-(U3-PACK)") (class "Default")
      (node (ref "C27") (pin "2") (pinfunction "2_2") (pintype "passive"))
      (node (ref "R29") (pin "1") (pinfunction "1_1") (pintype "passive"))
      (node (ref "U3") (pin "25") (pinfunction "PACK_25") (pintype "input"))
    )
    (net (code "38") (name "Net-(U3-PBI)") (class "Default")
      (node (ref "C26") (pin "2") (pinfunction "2_2") (pintype "passive"))
      (node (ref "U3") (pin "31") (pinfunction "PBI_31") (pintype "power_in"))
    )
    (net (code "39") (name "Net-(U3-SMBC)") (class "Default")
      (node (ref "R36") (pin "2") (pinfunction "2_2") (pintype "passive"))
      (node (ref "U3") (pin "19") (pinfunction "SMBC_19") (pintype "bidirectional"))
    )
    (net (code "40") (name "Net-(U3-SMBD)") (class "Default")
      (node (ref "R39") (pin "2") (pinfunction "2_2") (pintype "passive"))
      (node (ref "U3") (pin "18") (pinfunction "SMBD_18") (pintype "bidirectional"))
    )
    (net (code "41") (name "Net-(U3-VC1)") (class "Default")
      (node (ref "C32") (pin "1") (pinfunction "1_1") (pintype "passive"))
      (node (ref "R35") (pin "2") (pinfunction "2_2") (pintype "passive"))
      (node (ref "U3") (pin "5") (pinfunction "VC1_5") (pintype "input"))
    )
    (net (code "42") (name "Net-(U3-VC2)") (class "Default")
      (node (ref "C31") (pin "1") (pinfunction "1_1") (pintype "passive"))
      (node (ref "C32") (pin "2") (pinfunction "2_2") (pintype "passive"))
      (node (ref "R33") (pin "2") (pinfunction "2_2") (pintype "passive"))
      (node (ref "U3") (pin "4") (pinfunction "VC2_4") (pintype "input"))
    )
    (net (code "43") (name "Net-(U3-VC3)") (class "Default")
      (node (ref "C30") (pin "1") (pinfunction "1_1") (pintype "passive"))
      (node (ref "C31") (pin "2") (pinfunction "2_2") (pintype "passive"))
      (node (ref "R32") (pin "2") (pinfunction "2_2") (pintype "passive"))
      (node (ref "U3") (pin "3") (pinfunction "VC3_3") (pintype "input"))
    )
    (net (code "44") (name "Net-(U3-VC4)") (class "Default")
      (node (ref "C28") (pin "1") (pinfunction "1_1") (pintype "passive"))
      (node (ref "C30") (pin "2") (pinfunction "2_2") (pintype "passive"))
      (node (ref "R31") (pin "2") (pinfunction "2_2") (pintype "passive"))
      (node (ref "U3") (pin "2") (pinfunction "VC4_2") (pintype "input"))
    )
    (net (code "45") (name "Net-(U3-VC5)") (class "Default")
      (node (ref "C25") (pin "1") (pinfunction "1_1") (pintype "passive"))
      (node (ref "C28") (pin "2") (pinfunction "2_2") (pintype "passive"))
      (node (ref "R30") (pin "2") (pinfunction "2_2") (pintype "passive"))
      (node (ref "U3") (pin "1") (pinfunction "VC5_1") (pintype "input"))
    )
    (net (code "46") (name "Net-(U3-VC6)") (class "Default")
      (node (ref "C25") (pin "2") (pinfunction "2_2") (pintype "passive"))
      (node (ref "R25") (pin "2") (pinfunction "2_2") (pintype "passive"))
      (node (ref "U3") (pin "32") (pinfunction "VC6_32") (pintype "input"))
    )
    (net (code "47") (name "Net-(U3-VCC)") (class "Default")
      (node (ref "C21") (pin "2") (pinfunction "2_2") (pintype "passive"))
      (node (ref "C23") (pin "2") (pinfunction "2_2") (pintype "passive"))
      (node (ref "R22") (pin "1") (pinfunction "1_1") (pintype "passive"))
      (node (ref "U3") (pin "24") (pinfunction "VCC_24") (pintype "power_in"))
    )
    (net (code "48") (name "VBAT") (class "Default")
      (node (ref "C19") (pin "1") (pinfunction "1_1") (pintype "passive"))
      (node (ref "D7") (pin "2") (pintype "passive"))
      (node (ref "Q3") (pin "2") (pinfunction "Source_2") (pintype "passive"))
      (node (ref "Q5") (pin "2") (pinfunction "Source_2") (pintype "passive"))
      (node (ref "R16") (pin "1") (pinfunction "1_1") (pintype "passive"))
      (node (ref "R19") (pin "2") (pinfunction "2_2") (pintype "passive"))
      (node (ref "R25") (pin "1") (pinfunction "1_1") (pintype "passive"))
    )
  )
)
